# ESP8266.net
KiCad netlist of a schematic drawn in EAGLE
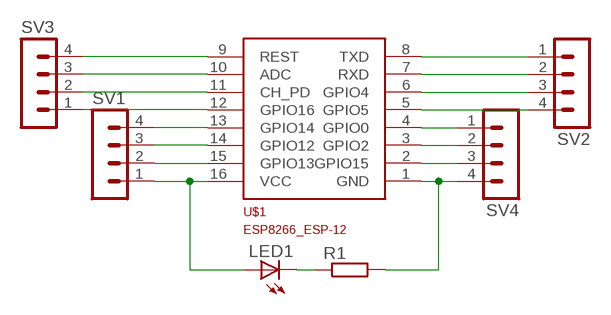
[diagram p0: schematic, sheet 1]

(export (version "E")
  (design (tool "Eeschema 10.0.6"))
  (components
    (comp (ref "LED1")
      (value "LEDSML0805")
      (footprint "eagle-import:SML0805")
      (libsource (lib "eagle-import") (part "LEDSML0805"))
    )
    (comp (ref "R1")
      (value "R-EU_R0805")
      (footprint "eagle-import:R0805")
      (libsource (lib "eagle-import") (part "R-EU_R0805"))
    )
    (comp (ref "SV1")
      (value "MA04-1")
      (footprint "eagle-import:MA04-1")
      (libsource (lib "eagle-import") (part "MA04-1"))
    )
    (comp (ref "SV2")
      (value "MA04-1")
      (footprint "eagle-import:MA04-1")
      (libsource (lib "eagle-import") (part "MA04-1"))
    )
    (comp (ref "SV3")
      (value "MA04-1")
      (footprint "eagle-import:MA04-1")
      (libsource (lib "eagle-import") (part "MA04-1"))
    )
    (comp (ref "SV4")
      (value "MA04-1")
      (footprint "eagle-import:MA04-1")
      (libsource (lib "eagle-import") (part "MA04-1"))
    )
    (comp (ref "U$1")
      (value "ESP8266_ESP-12")
      (footprint "eagle-import:ESP8266-ESP12")
      (libsource (lib "eagle-import") (part "ESP8266_ESP-12"))
    )
  )
  (nets
    (net (code "1") (name "Net-(LED1-PadC)") (class "Default")
      (node (ref "LED1") (pin "C") (pinfunction "C_C") (pintype "passive"))
      (node (ref "R1") (pin "1") (pinfunction "1_1") (pintype "passive"))
    )
    (net (code "2") (name "Net-(U$1-ADC)") (class "Default")
      (node (ref "SV3") (pin "3") (pinfunction "3_3") (pintype "passive"))
      (node (ref "U$1") (pin "10") (pinfunction "ADC_10") (pintype "bidirectional"))
    )
    (net (code "3") (name "Net-(U$1-CH_PD)") (class "Default")
      (node (ref "SV3") (pin "2") (pinfunction "2_2") (pintype "passive"))
      (node (ref "U$1") (pin "11") (pinfunction "CH_PD_11") (pintype "bidirectional"))
    )
    (net (code "4") (name "Net-(U$1-GND)") (class "Default")
      (node (ref "R1") (pin "2") (pinfunction "2_2") (pintype "passive"))
      (node (ref "SV4") (pin "4") (pinfunction "4_4") (pintype "passive"))
      (node (ref "U$1") (pin "1") (pinfunction "GND_1") (pintype "bidirectional"))
    )
    (net (code "5") (name "Net-(U$1-GPIO0)") (class "Default")
      (node (ref "SV4") (pin "1") (pinfunction "1_1") (pintype "passive"))
      (node (ref "U$1") (pin "4") (pinfunction "GPIO0_4") (pintype "bidirectional"))
    )
    (net (code "6") (name "Net-(U$1-GPIO2)") (class "Default")
      (node (ref "SV4") (pin "2") (pinfunction "2_2") (pintype "passive"))
      (node (ref "U$1") (pin "3") (pinfunction "GPIO2_3") (pintype "bidirectional"))
    )
    (net (code "7") (name "Net-(U$1-GPIO4)") (class "Default")
      (node (ref "SV2") (pin "3") (pinfunction "3_3") (pintype "passive"))
      (node (ref "U$1") (pin "6") (pinfunction "GPIO4_6") (pintype "bidirectional"))
    )
    (net (code "8") (name "Net-(U$1-GPIO5)") (class "Default")
      (node (ref "SV2") (pin "4") (pinfunction "4_4") (pintype "passive"))
      (node (ref "U$1") (pin "5") (pinfunction "GPIO5_5") (pintype "bidirectional"))
    )
    (net (code "9") (name "Net-(U$1-GPIO12)") (class "Default")
      (node (ref "SV1") (pin "3") (pinfunction "3_3") (pintype "passive"))
      (node (ref "U$1") (pin "14") (pinfunction "GPIO12_14") (pintype "bidirectional"))
    )
    (net (code "10") (name "Net-(U$1-GPIO13)") (class "Default")
      (node (ref "SV1") (pin "2") (pinfunction "2_2") (pintype "passive"))
      (node (ref "U$1") (pin "15") (pinfunction "GPIO13_15") (pintype "bidirectional"))
    )
    (net (code "11") (name "Net-(U$1-GPIO14)") (class "Default")
      (node (ref "SV1") (pin "4") (pinfunction "4_4") (pintype "passive"))
      (node (ref "U$1") (pin "13") (pinfunction "GPIO14_13") (pintype "bidirectional"))
    )
    (net (code "12") (name "Net-(U$1-GPIO15)") (class "Default")
      (node (ref "SV4") (pin "3") (pinfunction "3_3") (pintype "passive"))
      (node (ref "U$1") (pin "2") (pinfunction "GPIO15_2") (pintype "bidirectional"))
    )
    (net (code "13") (name "Net-(U$1-GPIO16)") (class "Default")
      (node (ref "SV3") (pin "1") (pinfunction "1_1") (pintype "passive"))
      (node (ref "U$1") (pin "12") (pinfunction "GPIO16_12") (pintype "bidirectional"))
    )
    (net (code "14") (name "Net-(U$1-REST)") (class "Default")
      (node (ref "SV3") (pin "4") (pinfunction "4_4") (pintype "passive"))
      (node (ref "U$1") (pin "9") (pinfunction "REST_9") (pintype "bidirectional"))
    )
    (net (code "15") (name "Net-(U$1-RXD)") (class "Default")
      (node (ref "SV2") (pin "2") (pinfunction "2_2") (pintype "passive"))
      (node (ref "U$1") (pin "7") (pinfunction "RXD_7") (pintype "bidirectional"))
    )
    (net (code "16") (name "Net-(U$1-TXD)") (class "Default")
      (node (ref "SV2") (pin "1") (pinfunction "1_1") (pintype "passive"))
      (node (ref "U$1") (pin "8") (pinfunction "TXD_8") (pintype "bidirectional"))
    )
    (net (code "17") (name "Net-(U$1-VCC)") (class "Default")
      (node (ref "LED1") (pin "A") (pinfunction "A_A") (pintype "passive"))
      (node (ref "SV1") (pin "1") (pinfunction "1_1") (pintype "passive"))
      (node (ref "U$1") (pin "16") (pinfunction "VCC_16") (pintype "bidirectional"))
    )
  )
)
